# onekeyboard.net
KiCad netlist of a schematic drawn in EAGLE
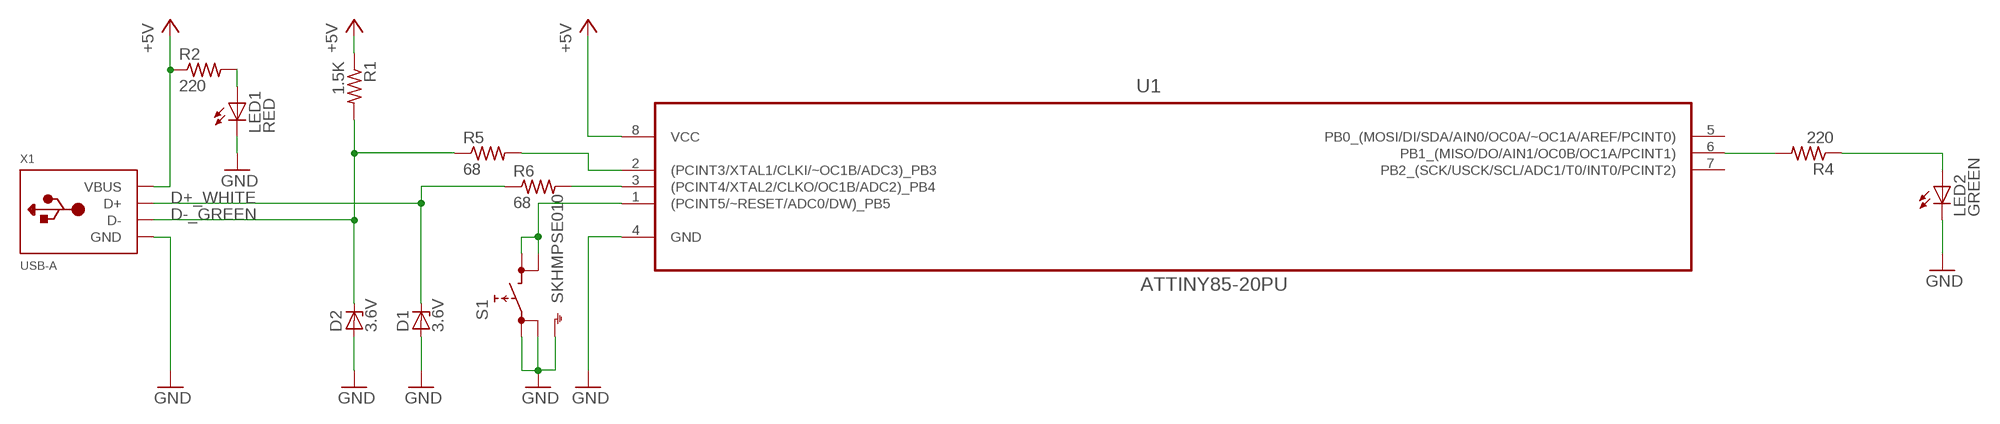
[diagram p0: schematic, sheet 1]

(export (version "E")
  (design (tool "Eeschema 10.0.6"))
  (components
    (comp (ref "D1")
      (value "3.6V")
      (footprint "eagle-import:DO41Z10")
      (libsource (lib "eagle-import") (part "1N4728"))
    )
    (comp (ref "D2")
      (value "3.6V")
      (footprint "eagle-import:DO41Z10")
      (libsource (lib "eagle-import") (part "1N4728"))
    )
    (comp (ref "LED1")
      (value "RED")
      (footprint "eagle-import:LED5MM")
      (libsource (lib "eagle-import") (part "LED5MM"))
    )
    (comp (ref "LED2")
      (value "GREEN")
      (footprint "eagle-import:LED5MM")
      (libsource (lib "eagle-import") (part "LED5MM"))
    )
    (comp (ref "R1")
      (value "1.5K")
      (footprint "eagle-import:0204_5")
      (libsource (lib "eagle-import") (part "R-US_0204/5"))
    )
    (comp (ref "R2")
      (value "220")
      (footprint "eagle-import:0204_5")
      (libsource (lib "eagle-import") (part "R-US_0204/5"))
    )
    (comp (ref "R4")
      (value "220")
      (footprint "eagle-import:0204_5")
      (libsource (lib "eagle-import") (part "R-US_0204/5"))
    )
    (comp (ref "R5")
      (value "68")
      (footprint "eagle-import:R0402")
      (libsource (lib "eagle-import") (part "R-US_R0402"))
    )
    (comp (ref "R6")
      (value "68")
      (footprint "eagle-import:R0402")
      (libsource (lib "eagle-import") (part "R-US_R0402"))
    )
    (comp (ref "S1")
      (value "SKHMPSE010")
      (footprint "eagle-import:SKHMPXE010")
      (libsource (lib "eagle-import") (part "SKHMPE010S"))
    )
    (comp (ref "U1")
      (value "ATTINY85-20PU")
      (footprint "eagle-import:DIP254P762X533-8")
      (libsource (lib "eagle-import") (part "ATTINY85-20PU"))
    )
    (comp (ref "X1")
      (value "USB-A")
      (footprint "eagle-import:MOLEX_480371000")
      (libsource (lib "eagle-import") (part "USB-A"))
    )
  )
  (nets
    (net (code "1") (name "+5V") (class "Default")
      (node (ref "R1") (pin "1") (pinfunction "1_1") (pintype "passive"))
      (node (ref "R2") (pin "1") (pinfunction "1_1") (pintype "passive"))
      (node (ref "U1") (pin "8") (pinfunction "VCC_8") (pintype "power_in"))
      (node (ref "X1") (pin "1") (pinfunction "VBUS_1") (pintype "power_in"))
    )
    (net (code "2") (name "/D+_WHITE") (class "Default")
      (node (ref "D1") (pin "C") (pinfunction "C_C") (pintype "passive"))
      (node (ref "R6") (pin "1") (pinfunction "1_1") (pintype "passive"))
      (node (ref "X1") (pin "3") (pinfunction "D+_3") (pintype "bidirectional"))
    )
    (net (code "3") (name "/D-_GREEN") (class "Default")
      (node (ref "D2") (pin "C") (pinfunction "C_C") (pintype "passive"))
      (node (ref "R1") (pin "2") (pinfunction "2_2") (pintype "passive"))
      (node (ref "R5") (pin "1") (pinfunction "1_1") (pintype "passive"))
      (node (ref "X1") (pin "2") (pinfunction "D-_2") (pintype "bidirectional"))
    )
    (net (code "4") (name "GND") (class "Default")
      (node (ref "D1") (pin "A") (pinfunction "A_A") (pintype "passive"))
      (node (ref "D2") (pin "A") (pinfunction "A_A") (pintype "passive"))
      (node (ref "LED1") (pin "K") (pinfunction "C_K") (pintype "passive"))
      (node (ref "LED2") (pin "K") (pinfunction "C_K") (pintype "passive"))
      (node (ref "S1") (pin "1") (pinfunction "1.1_1") (pintype "passive"))
      (node (ref "S1") (pin "2") (pinfunction "1.2_2") (pintype "passive"))
      (node (ref "S1") (pin "5") (pinfunction "SH_5") (pintype "passive"))
      (node (ref "U1") (pin "4") (pinfunction "GND_4") (pintype "passive"))
      (node (ref "X1") (pin "4") (pinfunction "GND_4") (pintype "power_in"))
    )
    (net (code "5") (name "Net-(LED1-PadA)") (class "Default")
      (node (ref "LED1") (pin "A") (pinfunction "A_A") (pintype "passive"))
      (node (ref "R2") (pin "2") (pinfunction "2_2") (pintype "passive"))
    )
    (net (code "6") (name "Net-(LED2-PadA)") (class "Default")
      (node (ref "LED2") (pin "A") (pinfunction "A_A") (pintype "passive"))
      (node (ref "R4") (pin "1") (pinfunction "1_1") (pintype "passive"))
    )
    (net (code "7") (name "Net-(S1-2.1)") (class "Default")
      (node (ref "S1") (pin "3") (pinfunction "2.1_3") (pintype "passive"))
      (node (ref "S1") (pin "4") (pinfunction "2.2_4") (pintype "passive"))
      (node (ref "U1") (pin "1") (pinfunction "(PCINT5/~{RESET/ADC0/DW})_PB5_1") (pintype "bidirectional"))
    )
    (net (code "8") (name "Net-(U1-(PCINT3{slash}XTAL1{slash}CLKI{slash}~{OC1B{slash}ADC3})_PB3)") (class "Default")
      (node (ref "R5") (pin "2") (pinfunction "2_2") (pintype "passive"))
      (node (ref "U1") (pin "2") (pinfunction "(PCINT3/XTAL1/CLKI/~{OC1B/ADC3})_PB3_2") (pintype "bidirectional"))
    )
    (net (code "9") (name "Net-(U1-(PCINT4{slash}XTAL2{slash}CLKO{slash}OC1B{slash}ADC2)_PB4)") (class "Default")
      (node (ref "R6") (pin "2") (pinfunction "2_2") (pintype "passive"))
      (node (ref "U1") (pin "3") (pinfunction "(PCINT4/XTAL2/CLKO/OC1B/ADC2)_PB4_3") (pintype "bidirectional"))
    )
    (net (code "10") (name "Net-(U1-PB1_(MISO{slash}DO{slash}AIN1{slash}OC0B{slash}OC1A{slash}PCINT1))") (class "Default")
      (node (ref "R4") (pin "2") (pinfunction "2_2") (pintype "passive"))
      (node (ref "U1") (pin "6") (pinfunction "PB1_(MISO/DO/AIN1/OC0B/OC1A/PCINT1)_6") (pintype "bidirectional"))
    )
    (net (code "11") (name "unconnected-(U1-PB0_(MOSI{slash}DI{slash}SDA{slash}AIN0{slash}OC0A{slash}~{OC1A{slash}AREF{slash}PCINT0})-Pad5)") (class "Default")
      (node (ref "U1") (pin "5") (pinfunction "PB0_(MOSI/DI/SDA/AIN0/OC0A/~{OC1A/AREF/PCINT0})_5") (pintype "bidirectional"))
    )
    (net (code "12") (name "unconnected-(U1-PB2_(SCK{slash}USCK{slash}SCL{slash}ADC1{slash}T0{slash}INT0{slash}PCINT2)-Pad7)") (class "Default")
      (node (ref "U1") (pin "7") (pinfunction "PB2_(SCK/USCK/SCL/ADC1/T0/INT0/PCINT2)_7") (pintype "bidirectional"))
    )
  )
)
